# LPCB219_-_LASER_DISTANCE.net
KiCad netlist of a schematic drawn in Altium Designer
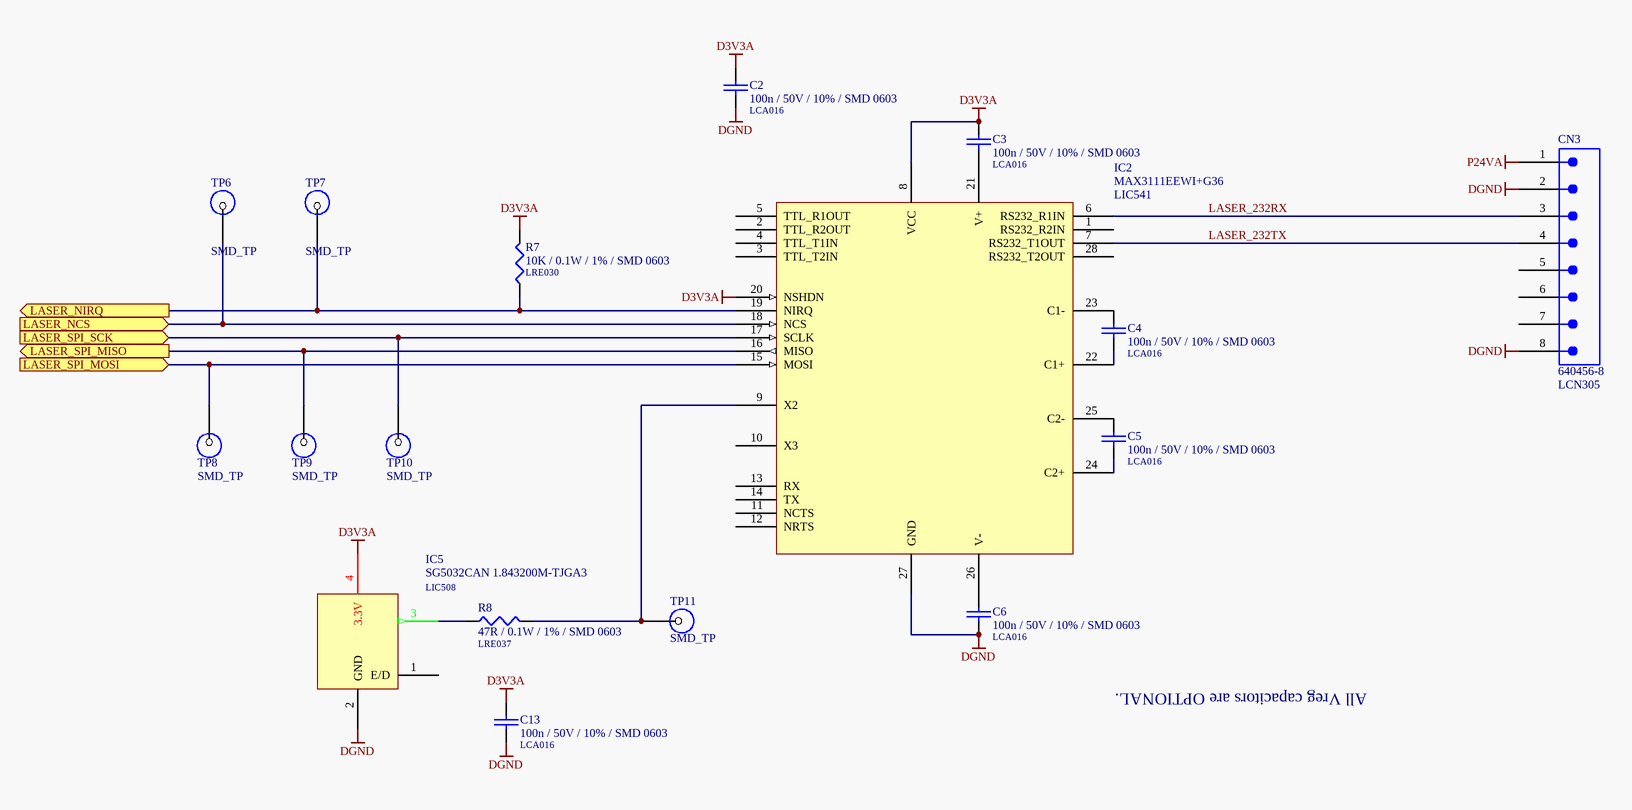
[diagram p0: LPCB219 - LASER DISTANCE.SchDoc]

(export (version "E")
  (design (tool "Eeschema 10.0.6"))
  (components
    (comp (ref "C2")
      (value "100n / 50V / 10% / SMD 0603")
      (footprint "LFP011__CC1608-0603-IPC7351_B")
      (description "Capacitor, Ceramic Chip, 100nF (0.1uF), 50V, 5%, SMD 0603 [LCA016]")
      (fields (field (name "LDL_NUMBER") "LCA016"))
      (libsource (lib "LDL_Capacitors") (part "100n / 50V / 10% / SMD 0603"))
    )
    (comp (ref "C3")
      (value "100n / 50V / 10% / SMD 0603")
      (footprint "LFP011__CC1608-0603-IPC7351_B")
      (description "Capacitor, Ceramic Chip, 100nF (0.1uF), 50V, 5%, SMD 0603 [LCA016]")
      (fields (field (name "LDL_NUMBER") "LCA016"))
      (libsource (lib "LDL_Capacitors") (part "100n / 50V / 10% / SMD 0603"))
    )
    (comp (ref "C4")
      (value "100n / 50V / 10% / SMD 0603")
      (footprint "LFP011__CC1608-0603-IPC7351_B")
      (description "Capacitor, Ceramic Chip, 100nF (0.1uF), 50V, 5%, SMD 0603 [LCA016]")
      (fields (field (name "LDL_NUMBER") "LCA016"))
      (libsource (lib "LDL_Capacitors") (part "100n / 50V / 10% / SMD 0603"))
    )
    (comp (ref "C5")
      (value "100n / 50V / 10% / SMD 0603")
      (footprint "LFP011__CC1608-0603-IPC7351_B")
      (description "Capacitor, Ceramic Chip, 100nF (0.1uF), 50V, 5%, SMD 0603 [LCA016]")
      (fields (field (name "LDL_NUMBER") "LCA016"))
      (libsource (lib "LDL_Capacitors") (part "100n / 50V / 10% / SMD 0603"))
    )
    (comp (ref "C6")
      (value "100n / 50V / 10% / SMD 0603")
      (footprint "LFP011__CC1608-0603-IPC7351_B")
      (description "Capacitor, Ceramic Chip, 100nF (0.1uF), 50V, 5%, SMD 0603 [LCA016]")
      (fields (field (name "LDL_NUMBER") "LCA016"))
      (libsource (lib "LDL_Capacitors") (part "100n / 50V / 10% / SMD 0603"))
    )
    (comp (ref "C13")
      (value "100n / 50V / 10% / SMD 0603")
      (footprint "LFP011__CC1608-0603-IPC7351_B")
      (description "Capacitor, Ceramic Chip, 100nF (0.1uF), 50V, 5%, SMD 0603 [LCA016]")
      (fields (field (name "LDL_NUMBER") "LCA016"))
      (libsource (lib "LDL_Capacitors") (part "100n / 50V / 10% / SMD 0603"))
    )
    (comp (ref "CN3")
      (value "640456-8")
      (footprint "640456-8")
      (description "Connector, Male Header, 8 Way")
      (fields (field (name "LDL_NUMBER") "LCN305"))
      (libsource (lib "LDL_Connectors") (part "640456-8"))
    )
    (comp (ref "IC2")
      (value "MAX3111EEWI+G36")
      (footprint "LFP024__SOIC300-28")
      (description "IC, SPI UART Interface, SMD SOIC28 [LIC541]")
      (fields (field (name "LDL_NUMBER") "LIC541"))
      (libsource (lib "LDL_Semiconductors") (part "MAX3111EEWI+G36"))
    )
    (comp (ref "IC5")
      (value "SG5032CAN 1.843200M-TJGA3")
      (footprint "LFP072__ASFLMB")
      (description "IC, Oscillator Module, 1.8432MHz, 3.3V, SMD [LIC508]")
      (fields (field (name "LDL_NUMBER") "LIC508"))
      (libsource (lib "LDL_Semiconductors") (part "SG5032CAN 1.843200M-TJGA3"))
    )
    (comp (ref "R7")
      (value "10K / 0.1W / 1% / SMD 0603")
      (footprint "LFP020__CR1608-0603-IPC7351_B")
      (description "Resistor, Ceramic Chip, 10K, 0.1W, 1%, SMD 0603 [LRE030]")
      (fields (field (name "LDL_NUMBER") "LRE030"))
      (libsource (lib "LDL_Resistors") (part "10K / 0.1W / 1% / SMD 0603"))
    )
    (comp (ref "R8")
      (value "47R / 0.1W / 1% / SMD 0603")
      (footprint "LFP020__CR1608-0603-IPC7351_B")
      (description "Resistor, Ceramic Chip, 47R, 0.1W, 1%, SMD 0603 [LRE037]")
      (fields (field (name "LDL_NUMBER") "LRE037"))
      (libsource (lib "LDL_Resistors") (part "47R / 0.1W / 1% / SMD 0603"))
    )
    (comp (ref "TP6")
      (value "SMD_TP")
      (footprint "SMD-TP")
      (description "SMD Test Point")
      (libsource (lib "LDL_Connectors") (part "SMD_TP"))
    )
    (comp (ref "TP7")
      (value "SMD_TP")
      (footprint "SMD-TP")
      (description "SMD Test Point")
      (libsource (lib "LDL_Connectors") (part "SMD_TP"))
    )
    (comp (ref "TP8")
      (value "SMD_TP")
      (footprint "SMD-TP")
      (description "SMD Test Point")
      (libsource (lib "LDL_Connectors") (part "SMD_TP"))
    )
    (comp (ref "TP9")
      (value "SMD_TP")
      (footprint "SMD-TP")
      (description "SMD Test Point")
      (libsource (lib "LDL_Connectors") (part "SMD_TP"))
    )
    (comp (ref "TP10")
      (value "SMD_TP")
      (footprint "SMD-TP")
      (description "SMD Test Point")
      (libsource (lib "LDL_Connectors") (part "SMD_TP"))
    )
    (comp (ref "TP11")
      (value "SMD_TP")
      (footprint "SMD-TP")
      (description "SMD Test Point")
      (libsource (lib "LDL_Connectors") (part "SMD_TP"))
    )
  )
  (nets
    (net (code "1") (name "/LASER_232RX") (class "Default")
      (node (ref "CN3") (pin "3") (pinfunction "3_3") (pintype "passive"))
      (node (ref "IC2") (pin "6") (pinfunction "RS232_R1IN_6") (pintype "passive"))
    )
    (net (code "2") (name "/LASER_232TX") (class "Default")
      (node (ref "CN3") (pin "4") (pinfunction "4_4") (pintype "passive"))
      (node (ref "IC2") (pin "7") (pinfunction "RS232_T1OUT_7") (pintype "passive"))
    )
    (net (code "3") (name "/LASER_NCS") (class "Default")
      (node (ref "IC2") (pin "18") (pinfunction "NCS_18") (pintype "input"))
      (node (ref "TP6") (pin "1") (pintype "passive"))
    )
    (net (code "4") (name "/LASER_NIRQ") (class "Default")
      (node (ref "IC2") (pin "19") (pinfunction "NIRQ_19") (pintype "passive"))
      (node (ref "R7") (pin "1") (pintype "passive"))
      (node (ref "TP7") (pin "1") (pintype "passive"))
    )
    (net (code "5") (name "/LASER_SPI_MISO") (class "Default")
      (node (ref "IC2") (pin "16") (pinfunction "MISO_16") (pintype "output"))
      (node (ref "TP9") (pin "1") (pintype "passive"))
    )
    (net (code "6") (name "/LASER_SPI_MOSI") (class "Default")
      (node (ref "IC2") (pin "15") (pinfunction "MOSI_15") (pintype "input"))
      (node (ref "TP8") (pin "1") (pintype "passive"))
    )
    (net (code "7") (name "/LASER_SPI_SCK") (class "Default")
      (node (ref "IC2") (pin "17") (pinfunction "SCLK_17") (pintype "input"))
      (node (ref "TP10") (pin "1") (pintype "passive"))
    )
    (net (code "8") (name "D3V3A") (class "Default")
      (node (ref "C13") (pin "1") (pintype "passive"))
      (node (ref "C2") (pin "1") (pintype "passive"))
      (node (ref "C3") (pin "1") (pintype "passive"))
      (node (ref "IC2") (pin "20") (pinfunction "NSHDN_20") (pintype "input"))
      (node (ref "IC2") (pin "8") (pinfunction "VCC_8") (pintype "power_in"))
      (node (ref "IC5") (pin "4") (pinfunction "3.3V_4") (pintype "power_in"))
      (node (ref "R7") (pin "2") (pintype "passive"))
    )
    (net (code "9") (name "DGND") (class "Default")
      (node (ref "C13") (pin "2") (pintype "passive"))
      (node (ref "C2") (pin "2") (pintype "passive"))
      (node (ref "C6") (pin "2") (pintype "passive"))
      (node (ref "CN3") (pin "2") (pinfunction "2_2") (pintype "passive"))
      (node (ref "CN3") (pin "8") (pinfunction "8_8") (pintype "passive"))
      (node (ref "IC2") (pin "27") (pinfunction "GND_27") (pintype "passive"))
      (node (ref "IC5") (pin "2") (pinfunction "GND_2") (pintype "power_in"))
    )
    (net (code "10") (name "Net-(IC2-C1+)") (class "Default")
      (node (ref "C4") (pin "2") (pintype "passive"))
      (node (ref "IC2") (pin "22") (pinfunction "C1+_22") (pintype "passive"))
    )
    (net (code "11") (name "Net-(IC2-C1-)") (class "Default")
      (node (ref "C4") (pin "1") (pintype "passive"))
      (node (ref "IC2") (pin "23") (pinfunction "C1-_23") (pintype "passive"))
    )
    (net (code "12") (name "Net-(IC2-C2+)") (class "Default")
      (node (ref "C5") (pin "2") (pintype "passive"))
      (node (ref "IC2") (pin "24") (pinfunction "C2+_24") (pintype "passive"))
    )
    (net (code "13") (name "Net-(IC2-C2-)") (class "Default")
      (node (ref "C5") (pin "1") (pintype "passive"))
      (node (ref "IC2") (pin "25") (pinfunction "C2-_25") (pintype "passive"))
    )
    (net (code "14") (name "Net-(IC2-V+)") (class "Default")
      (node (ref "C3") (pin "2") (pintype "passive"))
      (node (ref "IC2") (pin "21") (pinfunction "V+_21") (pintype "passive"))
    )
    (net (code "15") (name "Net-(IC2-V-)") (class "Default")
      (node (ref "C6") (pin "1") (pintype "passive"))
      (node (ref "IC2") (pin "26") (pinfunction "V-_26") (pintype "passive"))
    )
    (net (code "16") (name "Net-(IC2-X2)") (class "Default")
      (node (ref "IC2") (pin "9") (pinfunction "X2_9") (pintype "passive"))
      (node (ref "R8") (pin "2") (pintype "passive"))
      (node (ref "TP11") (pin "1") (pintype "passive"))
    )
    (net (code "17") (name "Net-(IC5-OUT)") (class "Default")
      (node (ref "IC5") (pin "3") (pinfunction "OUT_3") (pintype "output"))
      (node (ref "R8") (pin "1") (pintype "passive"))
    )
    (net (code "18") (name "P24VA") (class "Default")
      (node (ref "CN3") (pin "1") (pinfunction "1_1") (pintype "passive"))
    )
    (net (code "19") (name "unconnected-(CN3-Pad5)") (class "Default")
      (node (ref "CN3") (pin "5") (pinfunction "5_5") (pintype "passive"))
    )
    (net (code "20") (name "unconnected-(CN3-Pad6)") (class "Default")
      (node (ref "CN3") (pin "6") (pinfunction "6_6") (pintype "passive"))
    )
    (net (code "21") (name "unconnected-(CN3-Pad7)") (class "Default")
      (node (ref "CN3") (pin "7") (pinfunction "7_7") (pintype "passive"))
    )
    (net (code "22") (name "unconnected-(IC2-NCTS-Pad11)") (class "Default")
      (node (ref "IC2") (pin "11") (pinfunction "NCTS_11") (pintype "passive"))
    )
    (net (code "23") (name "unconnected-(IC2-NRTS-Pad12)") (class "Default")
      (node (ref "IC2") (pin "12") (pinfunction "NRTS_12") (pintype "passive"))
    )
    (net (code "24") (name "unconnected-(IC2-RS232_R2IN-Pad1)") (class "Default")
      (node (ref "IC2") (pin "1") (pinfunction "RS232_R2IN_1") (pintype "passive"))
    )
    (net (code "25") (name "unconnected-(IC2-RS232_T2OUT-Pad28)") (class "Default")
      (node (ref "IC2") (pin "28") (pinfunction "RS232_T2OUT_28") (pintype "passive"))
    )
    (net (code "26") (name "unconnected-(IC2-RX-Pad13)") (class "Default")
      (node (ref "IC2") (pin "13") (pinfunction "RX_13") (pintype "passive"))
    )
    (net (code "27") (name "unconnected-(IC2-TTL_R1OUT-Pad5)") (class "Default")
      (node (ref "IC2") (pin "5") (pinfunction "TTL_R1OUT_5") (pintype "passive"))
    )
    (net (code "28") (name "unconnected-(IC2-TTL_R2OUT-Pad2)") (class "Default")
      (node (ref "IC2") (pin "2") (pinfunction "TTL_R2OUT_2") (pintype "passive"))
    )
    (net (code "29") (name "unconnected-(IC2-TTL_T1IN-Pad4)") (class "Default")
      (node (ref "IC2") (pin "4") (pinfunction "TTL_T1IN_4") (pintype "passive"))
    )
    (net (code "30") (name "unconnected-(IC2-TTL_T2IN-Pad3)") (class "Default")
      (node (ref "IC2") (pin "3") (pinfunction "TTL_T2IN_3") (pintype "passive"))
    )
    (net (code "31") (name "unconnected-(IC2-TX-Pad14)") (class "Default")
      (node (ref "IC2") (pin "14") (pinfunction "TX_14") (pintype "passive"))
    )
    (net (code "32") (name "unconnected-(IC2-X3-Pad10)") (class "Default")
      (node (ref "IC2") (pin "10") (pinfunction "X3_10") (pintype "passive"))
    )
    (net (code "33") (name "unconnected-(IC5-E{slash}D-Pad1)") (class "Default")
      (node (ref "IC5") (pin "1") (pinfunction "E/D_1") (pintype "passive"))
    )
  )
)
